# Adapter_UARTSPI_RS485_1.net
KiCad netlist of a schematic drawn in Altium Designer
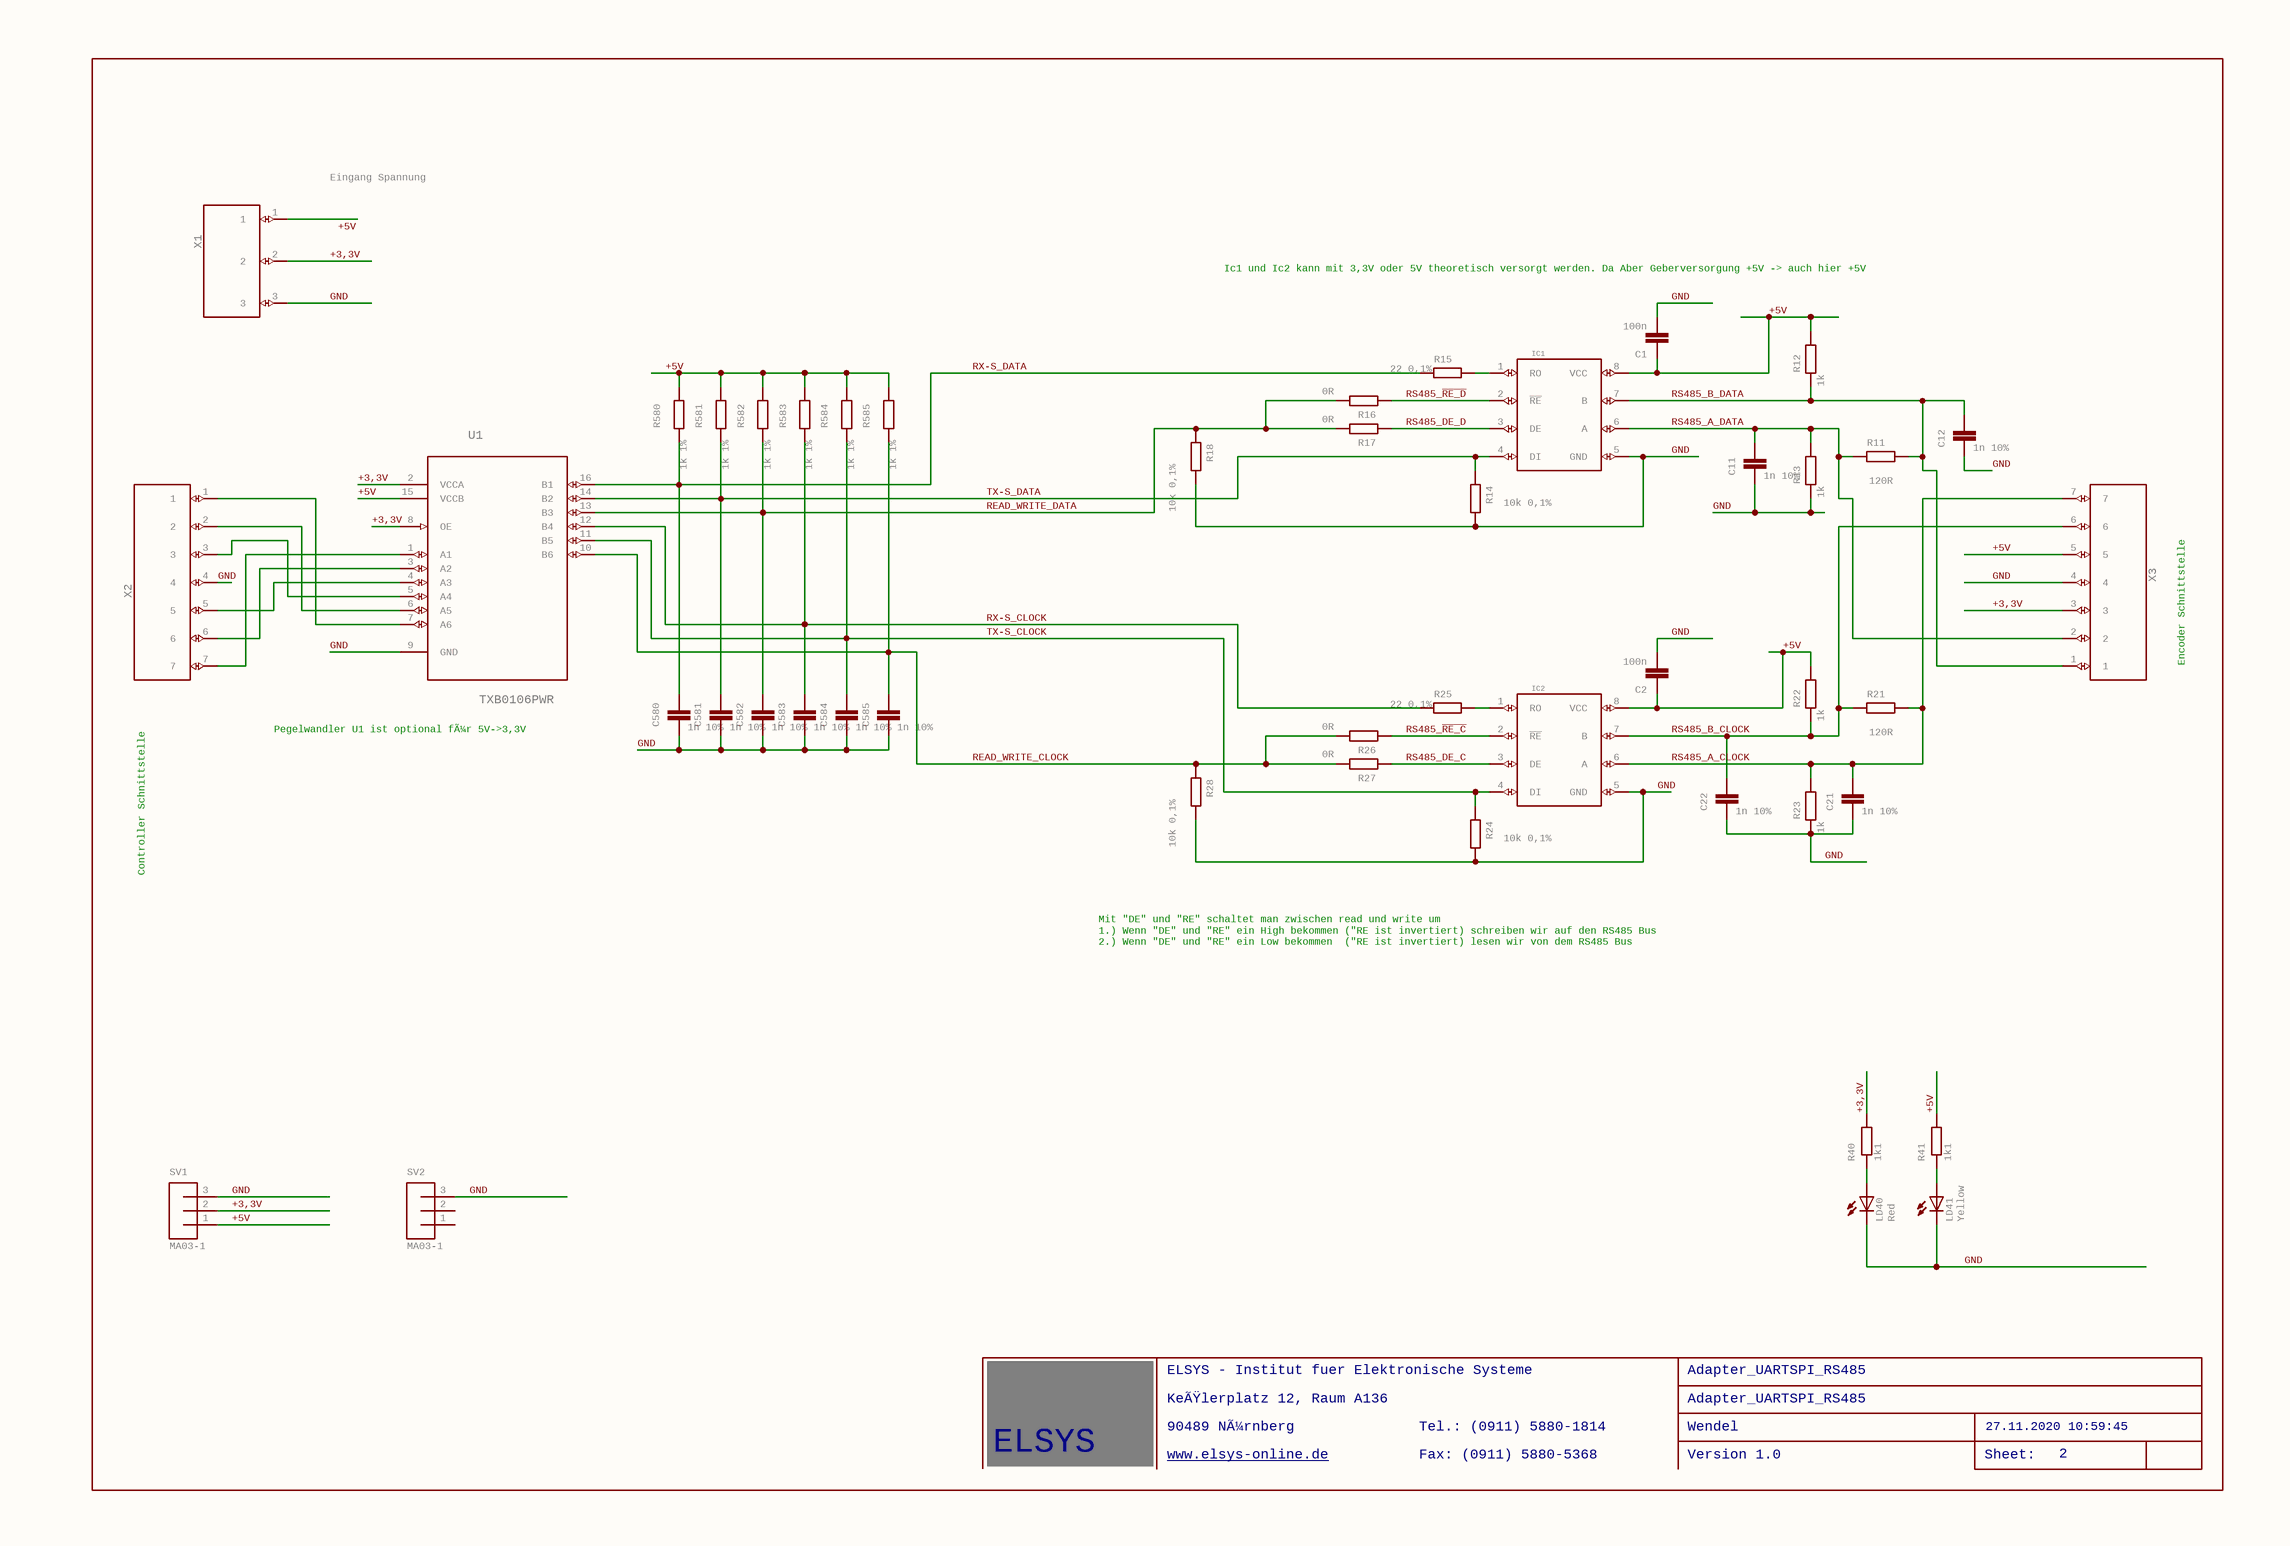
[diagram p0: Adapter_UARTSPI_RS485_1.SchDoc]

(export (version "E")
  (design (tool "Eeschema 10.0.6"))
  (components
    (comp (ref "C1")
      (value "100n")
      (footprint "SMD-0603")
      (description "CAPACITOR, European symbol")
      (fields (field (name "LIBRARYNAME") "Elsys - Kondenstatoren"))
      (libsource (lib "") (part "C-EU0603_1"))
    )
    (comp (ref "C2")
      (value "100n")
      (footprint "SMD-0603")
      (description "CAPACITOR, European symbol")
      (fields (field (name "LIBRARYNAME") "Elsys - Kondenstatoren"))
      (libsource (lib "") (part "C-EU0603_1"))
    )
    (comp (ref "C11")
      (value "1n 10%")
      (footprint "SMD-0603")
      (description "CAPACITOR, European symbol")
      (fields (field (name "LIBRARYNAME") "Elsys - Kondenstatoren"))
      (libsource (lib "Elsys - Kondenstatoren") (part "C-EU0603"))
    )
    (comp (ref "C12")
      (value "1n 10%")
      (footprint "SMD-0603")
      (description "CAPACITOR, European symbol")
      (fields (field (name "LIBRARYNAME") "Elsys - Kondenstatoren"))
      (libsource (lib "Elsys - Kondenstatoren") (part "C-EU0603"))
    )
    (comp (ref "C21")
      (value "1n 10%")
      (footprint "SMD-0603")
      (description "CAPACITOR, European symbol")
      (fields (field (name "LIBRARYNAME") "Elsys - Kondenstatoren"))
      (libsource (lib "Elsys - Kondenstatoren") (part "C-EU0603"))
    )
    (comp (ref "C22")
      (value "1n 10%")
      (footprint "SMD-0603")
      (description "CAPACITOR, European symbol")
      (fields (field (name "LIBRARYNAME") "Elsys - Kondenstatoren"))
      (libsource (lib "Elsys - Kondenstatoren") (part "C-EU0603"))
    )
    (comp (ref "C580")
      (value "1n 10%")
      (footprint "SMD-0603")
      (description "CAPACITOR, European symbol")
      (fields (field (name "LIBRARYNAME") "Elsys - Kondenstatoren"))
      (libsource (lib "Elsys - Kondenstatoren") (part "C-EU0603"))
    )
    (comp (ref "C581")
      (value "1n 10%")
      (footprint "SMD-0603")
      (description "CAPACITOR, European symbol")
      (fields (field (name "LIBRARYNAME") "Elsys - Kondenstatoren"))
      (libsource (lib "Elsys - Kondenstatoren") (part "C-EU0603"))
    )
    (comp (ref "C582")
      (value "1n 10%")
      (footprint "SMD-0603")
      (description "CAPACITOR, European symbol")
      (fields (field (name "LIBRARYNAME") "Elsys - Kondenstatoren"))
      (libsource (lib "Elsys - Kondenstatoren") (part "C-EU0603"))
    )
    (comp (ref "C583")
      (value "1n 10%")
      (footprint "SMD-0603")
      (description "CAPACITOR, European symbol")
      (fields (field (name "LIBRARYNAME") "Elsys - Kondenstatoren"))
      (libsource (lib "Elsys - Kondenstatoren") (part "C-EU0603"))
    )
    (comp (ref "C584")
      (value "1n 10%")
      (footprint "SMD-0603")
      (description "CAPACITOR, European symbol")
      (fields (field (name "LIBRARYNAME") "Elsys - Kondenstatoren"))
      (libsource (lib "Elsys - Kondenstatoren") (part "C-EU0603"))
    )
    (comp (ref "C585")
      (value "1n 10%")
      (footprint "SMD-0603")
      (description "CAPACITOR, European symbol")
      (fields (field (name "LIBRARYNAME") "Elsys - Kondenstatoren"))
      (libsource (lib "Elsys - Kondenstatoren") (part "C-EU0603"))
    )
    (comp (ref "IC1")
      (value "RS485-MAXIM")
      (footprint "SOIC8")
      (fields (field (name "LIBRARYNAME") "ELSYS - Symetrierung"))
      (libsource (lib "ELSYS - Symetrierung") (part "RS485-MAXIM"))
    )
    (comp (ref "IC2")
      (value "RS485-MAXIM")
      (footprint "SOIC8")
      (fields (field (name "LIBRARYNAME") "ELSYS - Symetrierung"))
      (libsource (lib "ELSYS - Symetrierung") (part "RS485-MAXIM"))
    )
    (comp (ref "LD40")
      (value "Red")
      (footprint "CHIP-LED0805")
      (libsource (lib "led (2)") (part "LEDCHIP-LED0805"))
    )
    (comp (ref "LD41")
      (value "Yellow")
      (footprint "CHIP-LED0805")
      (libsource (lib "led (2)") (part "LEDCHIP-LED0805"))
    )
    (comp (ref "R11")
      (value "120R")
      (footprint "R0603")
      (description "RESISTOR, European symbol")
      (fields (field (name "LIBRARYNAME") "Elsys - Widerstaende"))
      (libsource (lib "Elsys - Widerstaende") (part "R-EU_R0603"))
    )
    (comp (ref "R12")
      (value "1k")
      (footprint "R0603")
      (description "RESISTOR, European symbol")
      (fields (field (name "LIBRARYNAME") "Elsys - Widerstaende"))
      (libsource (lib "Elsys - Widerstaende") (part "R-EU_R0603"))
    )
    (comp (ref "R13")
      (value "1k")
      (footprint "R0603")
      (description "RESISTOR, European symbol")
      (fields (field (name "LIBRARYNAME") "Elsys - Widerstaende"))
      (libsource (lib "Elsys - Widerstaende") (part "R-EU_R0603"))
    )
    (comp (ref "R14")
      (value "10k 0,1%")
      (footprint "R0603")
      (description "RESISTOR, European symbol")
      (fields (field (name "LIBRARYNAME") "Elsys - Widerstaende"))
      (libsource (lib "Elsys - Widerstaende") (part "R-EU_R0603"))
    )
    (comp (ref "R15")
      (value "22 0,1%")
      (footprint "R0603")
      (description "RESISTOR, European symbol")
      (fields (field (name "LIBRARYNAME") "Elsys - Widerstaende"))
      (libsource (lib "Elsys - Widerstaende") (part "R-EU_R0603"))
    )
    (comp (ref "R16")
      (value "0R")
      (footprint "R0603")
      (description "RESISTOR, European symbol")
      (fields (field (name "LIBRARYNAME") "Elsys - Widerstaende"))
      (libsource (lib "Elsys - Widerstaende") (part "R-EU_R0603"))
    )
    (comp (ref "R17")
      (value "0R")
      (footprint "R0603")
      (description "RESISTOR, European symbol")
      (fields (field (name "LIBRARYNAME") "Elsys - Widerstaende"))
      (libsource (lib "Elsys - Widerstaende") (part "R-EU_R0603"))
    )
    (comp (ref "R18")
      (value "10k 0,1%")
      (footprint "R0603")
      (description "RESISTOR, European symbol")
      (fields (field (name "LIBRARYNAME") "Elsys - Widerstaende"))
      (libsource (lib "Elsys - Widerstaende") (part "R-EU_R0603"))
    )
    (comp (ref "R21")
      (value "120R")
      (footprint "R0603")
      (description "RESISTOR, European symbol")
      (fields (field (name "LIBRARYNAME") "Elsys - Widerstaende"))
      (libsource (lib "Elsys - Widerstaende") (part "R-EU_R0603"))
    )
    (comp (ref "R22")
      (value "1k")
      (footprint "R0603")
      (description "RESISTOR, European symbol")
      (fields (field (name "LIBRARYNAME") "Elsys - Widerstaende"))
      (libsource (lib "Elsys - Widerstaende") (part "R-EU_R0603"))
    )
    (comp (ref "R23")
      (value "1k")
      (footprint "R0603")
      (description "RESISTOR, European symbol")
      (fields (field (name "LIBRARYNAME") "Elsys - Widerstaende"))
      (libsource (lib "Elsys - Widerstaende") (part "R-EU_R0603"))
    )
    (comp (ref "R24")
      (value "10k 0,1%")
      (footprint "R0603")
      (description "RESISTOR, European symbol")
      (fields (field (name "LIBRARYNAME") "Elsys - Widerstaende"))
      (libsource (lib "Elsys - Widerstaende") (part "R-EU_R0603"))
    )
    (comp (ref "R25")
      (value "22 0,1%")
      (footprint "R0603")
      (description "RESISTOR, European symbol")
      (fields (field (name "LIBRARYNAME") "Elsys - Widerstaende"))
      (libsource (lib "Elsys - Widerstaende") (part "R-EU_R0603"))
    )
    (comp (ref "R26")
      (value "0R")
      (footprint "R0603")
      (description "RESISTOR, European symbol")
      (fields (field (name "LIBRARYNAME") "Elsys - Widerstaende"))
      (libsource (lib "Elsys - Widerstaende") (part "R-EU_R0603"))
    )
    (comp (ref "R27")
      (value "0R")
      (footprint "R0603")
      (description "RESISTOR, European symbol")
      (fields (field (name "LIBRARYNAME") "Elsys - Widerstaende"))
      (libsource (lib "Elsys - Widerstaende") (part "R-EU_R0603"))
    )
    (comp (ref "R28")
      (value "10k 0,1%")
      (footprint "R0603")
      (description "RESISTOR, European symbol")
      (fields (field (name "LIBRARYNAME") "Elsys - Widerstaende"))
      (libsource (lib "Elsys - Widerstaende") (part "R-EU_R0603"))
    )
    (comp (ref "R40")
      (value "1k1")
      (footprint "R0805")
      (description "RESISTOR, European symbol")
      (fields (field (name "LIBRARYNAME") "Elsys - Widerstaende"))
      (libsource (lib "Elsys - Widerstaende") (part "R-EU_R0805"))
    )
    (comp (ref "R41")
      (value "1k1")
      (footprint "R0805")
      (description "RESISTOR, European symbol")
      (fields (field (name "LIBRARYNAME") "Elsys - Widerstaende"))
      (libsource (lib "Elsys - Widerstaende") (part "R-EU_R0805"))
    )
    (comp (ref "R580")
      (value "1k 1%")
      (footprint "R0603")
      (description "RESISTOR, European symbol")
      (fields (field (name "LIBRARYNAME") "Elsys - Widerstaende"))
      (libsource (lib "Elsys - Widerstaende") (part "R-EU_R0603"))
    )
    (comp (ref "R581")
      (value "1k 1%")
      (footprint "R0603")
      (description "RESISTOR, European symbol")
      (fields (field (name "LIBRARYNAME") "Elsys - Widerstaende"))
      (libsource (lib "Elsys - Widerstaende") (part "R-EU_R0603"))
    )
    (comp (ref "R582")
      (value "1k 1%")
      (footprint "R0603")
      (description "RESISTOR, European symbol")
      (fields (field (name "LIBRARYNAME") "Elsys - Widerstaende"))
      (libsource (lib "Elsys - Widerstaende") (part "R-EU_R0603"))
    )
    (comp (ref "R583")
      (value "1k 1%")
      (footprint "R0603")
      (description "RESISTOR, European symbol")
      (fields (field (name "LIBRARYNAME") "Elsys - Widerstaende"))
      (libsource (lib "Elsys - Widerstaende") (part "R-EU_R0603"))
    )
    (comp (ref "R584")
      (value "1k 1%")
      (footprint "R0603")
      (description "RESISTOR, European symbol")
      (fields (field (name "LIBRARYNAME") "Elsys - Widerstaende"))
      (libsource (lib "Elsys - Widerstaende") (part "R-EU_R0603"))
    )
    (comp (ref "R585")
      (value "1k 1%")
      (footprint "R0603")
      (description "RESISTOR, European symbol")
      (fields (field (name "LIBRARYNAME") "Elsys - Widerstaende"))
      (libsource (lib "Elsys - Widerstaende") (part "R-EU_R0603"))
    )
    (comp (ref "SV1")
      (value "MA03-1")
      (footprint "MA03-1")
      (description "PIN HEADER")
      (fields (field (name "LIBRARYNAME") "Elsys - Stiftleisten"))
      (libsource (lib "Elsys - Stiftleisten") (part "MA03-1"))
    )
    (comp (ref "SV2")
      (value "MA03-1")
      (footprint "MA03-1")
      (description "PIN HEADER")
      (fields (field (name "LIBRARYNAME") "Elsys - Stiftleisten"))
      (libsource (lib "Elsys - Stiftleisten") (part "MA03-1"))
    )
    (comp (ref "U1")
      (value "TXB0106PWR")
      (footprint "SOP65P640X120-16N")
      (description "VOLTAGE-LEVEL TRANSLATOR")
      (fields (field (name "LIBRARYNAME") "Texas Instruments_By_element14_Batch_1"))
      (libsource (lib "Texas Instruments_By_element14_Batch_1") (part "TXB0106PWR"))
    )
    (comp (ref "X1")
      (value "KLEMME_3POLIG_2,54")
      (footprint "KLEMME_3POLIG_2,54")
      (fields (field (name "LIBRARYNAME") "ELSYS - Symetrierung"))
      (libsource (lib "ELSYS - Symetrierung") (part "KLEMME_3POLIG_2,54"))
    )
    (comp (ref "X2")
      (value "KLEMME_7POLIG_2,54")
      (footprint "KLEMME_7POLIG_2,54")
      (fields (field (name "LIBRARYNAME") "ELSYS - Symetrierung"))
      (libsource (lib "ELSYS - Symetrierung") (part "KLEMME_7POLIG_2,54"))
    )
    (comp (ref "X3")
      (value "KLEMME_7POLIG_2,54")
      (footprint "KLEMME_7POLIG_2,54")
      (fields (field (name "LIBRARYNAME") "ELSYS - Symetrierung"))
      (libsource (lib "ELSYS - Symetrierung") (part "KLEMME_7POLIG_2,54"))
    )
  )
  (nets
    (net (code "1") (name "/+3,3V") (class "Default")
      (node (ref "R40") (pin "2") (pinfunction "2_2") (pintype "passive"))
      (node (ref "SV1") (pin "2") (pinfunction "2_2") (pintype "passive"))
      (node (ref "U1") (pin "2") (pinfunction "VCCA_2") (pintype "power_in"))
      (node (ref "U1") (pin "8") (pinfunction "OE_8") (pintype "input"))
      (node (ref "X1") (pin "2") (pinfunction "2_2") (pintype "bidirectional"))
      (node (ref "X3") (pin "3") (pinfunction "3_3") (pintype "bidirectional"))
    )
    (net (code "2") (name "/+5V") (class "Default")
      (node (ref "C1") (pin "1") (pinfunction "1_1") (pintype "passive"))
      (node (ref "C2") (pin "1") (pinfunction "1_1") (pintype "passive"))
      (node (ref "IC1") (pin "8") (pinfunction "VCC_8") (pintype "bidirectional"))
      (node (ref "IC2") (pin "8") (pinfunction "VCC_8") (pintype "bidirectional"))
      (node (ref "R12") (pin "1") (pinfunction "1_1") (pintype "passive"))
      (node (ref "R22") (pin "1") (pinfunction "1_1") (pintype "passive"))
      (node (ref "R41") (pin "2") (pinfunction "2_2") (pintype "passive"))
      (node (ref "R580") (pin "2") (pinfunction "2_2") (pintype "passive"))
      (node (ref "R581") (pin "2") (pinfunction "2_2") (pintype "passive"))
      (node (ref "R582") (pin "2") (pinfunction "2_2") (pintype "passive"))
      (node (ref "R583") (pin "2") (pinfunction "2_2") (pintype "passive"))
      (node (ref "R584") (pin "2") (pinfunction "2_2") (pintype "passive"))
      (node (ref "R585") (pin "2") (pinfunction "2_2") (pintype "passive"))
      (node (ref "SV1") (pin "1") (pinfunction "1_1") (pintype "passive"))
      (node (ref "U1") (pin "15") (pinfunction "VCCB_15") (pintype "power_in"))
      (node (ref "X1") (pin "1") (pinfunction "1_1") (pintype "bidirectional"))
      (node (ref "X3") (pin "5") (pinfunction "5_5") (pintype "bidirectional"))
    )
    (net (code "3") (name "/GND") (class "Default")
      (node (ref "C1") (pin "2") (pinfunction "2_2") (pintype "passive"))
      (node (ref "C11") (pin "2") (pinfunction "2_2") (pintype "passive"))
      (node (ref "C12") (pin "2") (pinfunction "2_2") (pintype "passive"))
      (node (ref "C2") (pin "2") (pinfunction "2_2") (pintype "passive"))
      (node (ref "C21") (pin "2") (pinfunction "2_2") (pintype "passive"))
      (node (ref "C22") (pin "2") (pinfunction "2_2") (pintype "passive"))
      (node (ref "C580") (pin "2") (pinfunction "2_2") (pintype "passive"))
      (node (ref "C581") (pin "2") (pinfunction "2_2") (pintype "passive"))
      (node (ref "C582") (pin "2") (pinfunction "2_2") (pintype "passive"))
      (node (ref "C583") (pin "2") (pinfunction "2_2") (pintype "passive"))
      (node (ref "C584") (pin "2") (pinfunction "2_2") (pintype "passive"))
      (node (ref "C585") (pin "2") (pinfunction "2_2") (pintype "passive"))
      (node (ref "IC1") (pin "5") (pinfunction "GND_5") (pintype "bidirectional"))
      (node (ref "IC2") (pin "5") (pinfunction "GND_5") (pintype "bidirectional"))
      (node (ref "LD40") (pin "C") (pinfunction "C_C") (pintype "passive"))
      (node (ref "LD41") (pin "C") (pinfunction "C_C") (pintype "passive"))
      (node (ref "R13") (pin "2") (pinfunction "2_2") (pintype "passive"))
      (node (ref "R14") (pin "1") (pinfunction "1_1") (pintype "passive"))
      (node (ref "R18") (pin "1") (pinfunction "1_1") (pintype "passive"))
      (node (ref "R23") (pin "2") (pinfunction "2_2") (pintype "passive"))
      (node (ref "R24") (pin "1") (pinfunction "1_1") (pintype "passive"))
      (node (ref "R28") (pin "1") (pinfunction "1_1") (pintype "passive"))
      (node (ref "SV1") (pin "3") (pinfunction "3_3") (pintype "passive"))
      (node (ref "SV2") (pin "3") (pinfunction "3_3") (pintype "passive"))
      (node (ref "U1") (pin "9") (pinfunction "GND_9") (pintype "passive"))
      (node (ref "X1") (pin "3") (pinfunction "3_3") (pintype "bidirectional"))
      (node (ref "X2") (pin "4") (pinfunction "4_4") (pintype "bidirectional"))
      (node (ref "X3") (pin "4") (pinfunction "4_4") (pintype "bidirectional"))
    )
    (net (code "4") (name "/READ_WRITE_CLOCK") (class "Default")
      (node (ref "C585") (pin "1") (pinfunction "1_1") (pintype "passive"))
      (node (ref "R26") (pin "1") (pinfunction "1_1") (pintype "passive"))
      (node (ref "R27") (pin "1") (pinfunction "1_1") (pintype "passive"))
      (node (ref "R28") (pin "2") (pinfunction "2_2") (pintype "passive"))
      (node (ref "R585") (pin "1") (pinfunction "1_1") (pintype "passive"))
      (node (ref "U1") (pin "10") (pinfunction "B6_10") (pintype "bidirectional"))
    )
    (net (code "5") (name "/READ_WRITE_DATA") (class "Default")
      (node (ref "C582") (pin "1") (pinfunction "1_1") (pintype "passive"))
      (node (ref "R16") (pin "1") (pinfunction "1_1") (pintype "passive"))
      (node (ref "R17") (pin "1") (pinfunction "1_1") (pintype "passive"))
      (node (ref "R18") (pin "2") (pinfunction "2_2") (pintype "passive"))
      (node (ref "R582") (pin "1") (pinfunction "1_1") (pintype "passive"))
      (node (ref "U1") (pin "13") (pinfunction "B3_13") (pintype "bidirectional"))
    )
    (net (code "6") (name "/RS485_A_CLOCK") (class "Default")
      (node (ref "C21") (pin "1") (pinfunction "1_1") (pintype "passive"))
      (node (ref "IC2") (pin "6") (pinfunction "A_6") (pintype "bidirectional"))
      (node (ref "R21") (pin "1") (pinfunction "1_1") (pintype "passive"))
      (node (ref "R23") (pin "1") (pinfunction "1_1") (pintype "passive"))
      (node (ref "X3") (pin "7") (pinfunction "7_7") (pintype "bidirectional"))
    )
    (net (code "7") (name "/RS485_A_DATA") (class "Default")
      (node (ref "C11") (pin "1") (pinfunction "1_1") (pintype "passive"))
      (node (ref "IC1") (pin "6") (pinfunction "A_6") (pintype "bidirectional"))
      (node (ref "R11") (pin "2") (pinfunction "2_2") (pintype "passive"))
      (node (ref "R13") (pin "1") (pinfunction "1_1") (pintype "passive"))
      (node (ref "X3") (pin "2") (pinfunction "2_2") (pintype "bidirectional"))
    )
    (net (code "8") (name "/RS485_B_CLOCK") (class "Default")
      (node (ref "C22") (pin "1") (pinfunction "1_1") (pintype "passive"))
      (node (ref "IC2") (pin "7") (pinfunction "B_7") (pintype "bidirectional"))
      (node (ref "R21") (pin "2") (pinfunction "2_2") (pintype "passive"))
      (node (ref "R22") (pin "2") (pinfunction "2_2") (pintype "passive"))
      (node (ref "X3") (pin "6") (pinfunction "6_6") (pintype "bidirectional"))
    )
    (net (code "9") (name "/RS485_B_DATA") (class "Default")
      (node (ref "C12") (pin "1") (pinfunction "1_1") (pintype "passive"))
      (node (ref "IC1") (pin "7") (pinfunction "B_7") (pintype "bidirectional"))
      (node (ref "R11") (pin "1") (pinfunction "1_1") (pintype "passive"))
      (node (ref "R12") (pin "2") (pinfunction "2_2") (pintype "passive"))
      (node (ref "X3") (pin "1") (pinfunction "1_1") (pintype "bidirectional"))
    )
    (net (code "10") (name "/RS485_DE_C") (class "Default")
      (node (ref "IC2") (pin "3") (pinfunction "DE_3") (pintype "bidirectional"))
      (node (ref "R27") (pin "2") (pinfunction "2_2") (pintype "passive"))
    )
    (net (code "11") (name "/RS485_DE_D") (class "Default")
      (node (ref "IC1") (pin "3") (pinfunction "DE_3") (pintype "bidirectional"))
      (node (ref "R17") (pin "2") (pinfunction "2_2") (pintype "passive"))
    )
    (net (code "12") (name "/RS485_~{RE_C}") (class "Default")
      (node (ref "IC2") (pin "2") (pinfunction "~{RE}_2") (pintype "bidirectional"))
      (node (ref "R26") (pin "2") (pinfunction "2_2") (pintype "passive"))
    )
    (net (code "13") (name "/RS485_~{RE_D}") (class "Default")
      (node (ref "IC1") (pin "2") (pinfunction "~{RE}_2") (pintype "bidirectional"))
      (node (ref "R16") (pin "2") (pinfunction "2_2") (pintype "passive"))
    )
    (net (code "14") (name "/RX-S_CLOCK") (class "Default")
      (node (ref "C583") (pin "1") (pinfunction "1_1") (pintype "passive"))
      (node (ref "R25") (pin "2") (pinfunction "2_2") (pintype "passive"))
      (node (ref "R583") (pin "1") (pinfunction "1_1") (pintype "passive"))
      (node (ref "U1") (pin "12") (pinfunction "B4_12") (pintype "bidirectional"))
    )
    (net (code "15") (name "/RX-S_DATA") (class "Default")
      (node (ref "C580") (pin "1") (pinfunction "1_1") (pintype "passive"))
      (node (ref "R15") (pin "2") (pinfunction "2_2") (pintype "passive"))
      (node (ref "R580") (pin "1") (pinfunction "1_1") (pintype "passive"))
      (node (ref "U1") (pin "16") (pinfunction "B1_16") (pintype "bidirectional"))
    )
    (net (code "16") (name "/TX-S_CLOCK") (class "Default")
      (node (ref "C584") (pin "1") (pinfunction "1_1") (pintype "passive"))
      (node (ref "IC2") (pin "4") (pinfunction "DI_4") (pintype "bidirectional"))
      (node (ref "R24") (pin "2") (pinfunction "2_2") (pintype "passive"))
      (node (ref "R584") (pin "1") (pinfunction "1_1") (pintype "passive"))
      (node (ref "U1") (pin "11") (pinfunction "B5_11") (pintype "bidirectional"))
    )
    (net (code "17") (name "/TX-S_DATA") (class "Default")
      (node (ref "C581") (pin "1") (pinfunction "1_1") (pintype "passive"))
      (node (ref "IC1") (pin "4") (pinfunction "DI_4") (pintype "bidirectional"))
      (node (ref "R14") (pin "2") (pinfunction "2_2") (pintype "passive"))
      (node (ref "R581") (pin "1") (pinfunction "1_1") (pintype "passive"))
      (node (ref "U1") (pin "14") (pinfunction "B2_14") (pintype "bidirectional"))
    )
    (net (code "18") (name "Net-(IC1-RO)") (class "Default")
      (node (ref "IC1") (pin "1") (pinfunction "RO_1") (pintype "bidirectional"))
      (node (ref "R15") (pin "1") (pinfunction "1_1") (pintype "passive"))
    )
    (net (code "19") (name "Net-(IC2-RO)") (class "Default")
      (node (ref "IC2") (pin "1") (pinfunction "RO_1") (pintype "bidirectional"))
      (node (ref "R25") (pin "1") (pinfunction "1_1") (pintype "passive"))
    )
    (net (code "20") (name "Net-(LD40-PadA)") (class "Default")
      (node (ref "LD40") (pin "A") (pinfunction "A_A") (pintype "passive"))
      (node (ref "R40") (pin "1") (pinfunction "1_1") (pintype "passive"))
    )
    (net (code "21") (name "Net-(LD41-PadA)") (class "Default")
      (node (ref "LD41") (pin "A") (pinfunction "A_A") (pintype "passive"))
      (node (ref "R41") (pin "1") (pinfunction "1_1") (pintype "passive"))
    )
    (net (code "22") (name "Net-(U1-A1)") (class "Default")
      (node (ref "U1") (pin "1") (pinfunction "A1_1") (pintype "bidirectional"))
      (node (ref "X2") (pin "7") (pinfunction "7_7") (pintype "bidirectional"))
    )
    (net (code "23") (name "Net-(U1-A2)") (class "Default")
      (node (ref "U1") (pin "3") (pinfunction "A2_3") (pintype "bidirectional"))
      (node (ref "X2") (pin "6") (pinfunction "6_6") (pintype "bidirectional"))
    )
    (net (code "24") (name "Net-(U1-A3)") (class "Default")
      (node (ref "U1") (pin "4") (pinfunction "A3_4") (pintype "bidirectional"))
      (node (ref "X2") (pin "5") (pinfunction "5_5") (pintype "bidirectional"))
    )
    (net (code "25") (name "Net-(U1-A4)") (class "Default")
      (node (ref "U1") (pin "5") (pinfunction "A4_5") (pintype "bidirectional"))
      (node (ref "X2") (pin "3") (pinfunction "3_3") (pintype "bidirectional"))
    )
    (net (code "26") (name "Net-(U1-A5)") (class "Default")
      (node (ref "U1") (pin "6") (pinfunction "A5_6") (pintype "bidirectional"))
      (node (ref "X2") (pin "2") (pinfunction "2_2") (pintype "bidirectional"))
    )
    (net (code "27") (name "Net-(U1-A6)") (class "Default")
      (node (ref "U1") (pin "7") (pinfunction "A6_7") (pintype "bidirectional"))
      (node (ref "X2") (pin "1") (pinfunction "1_1") (pintype "bidirectional"))
    )
    (net (code "28") (name "unconnected-(SV2-Pad1)") (class "Default")
      (node (ref "SV2") (pin "1") (pinfunction "1_1") (pintype "passive"))
    )
    (net (code "29") (name "unconnected-(SV2-Pad2)") (class "Default")
      (node (ref "SV2") (pin "2") (pinfunction "2_2") (pintype "passive"))
    )
  )
)
